# teensyMotors02_up.net
KiCad netlist of a schematic drawn in EAGLE
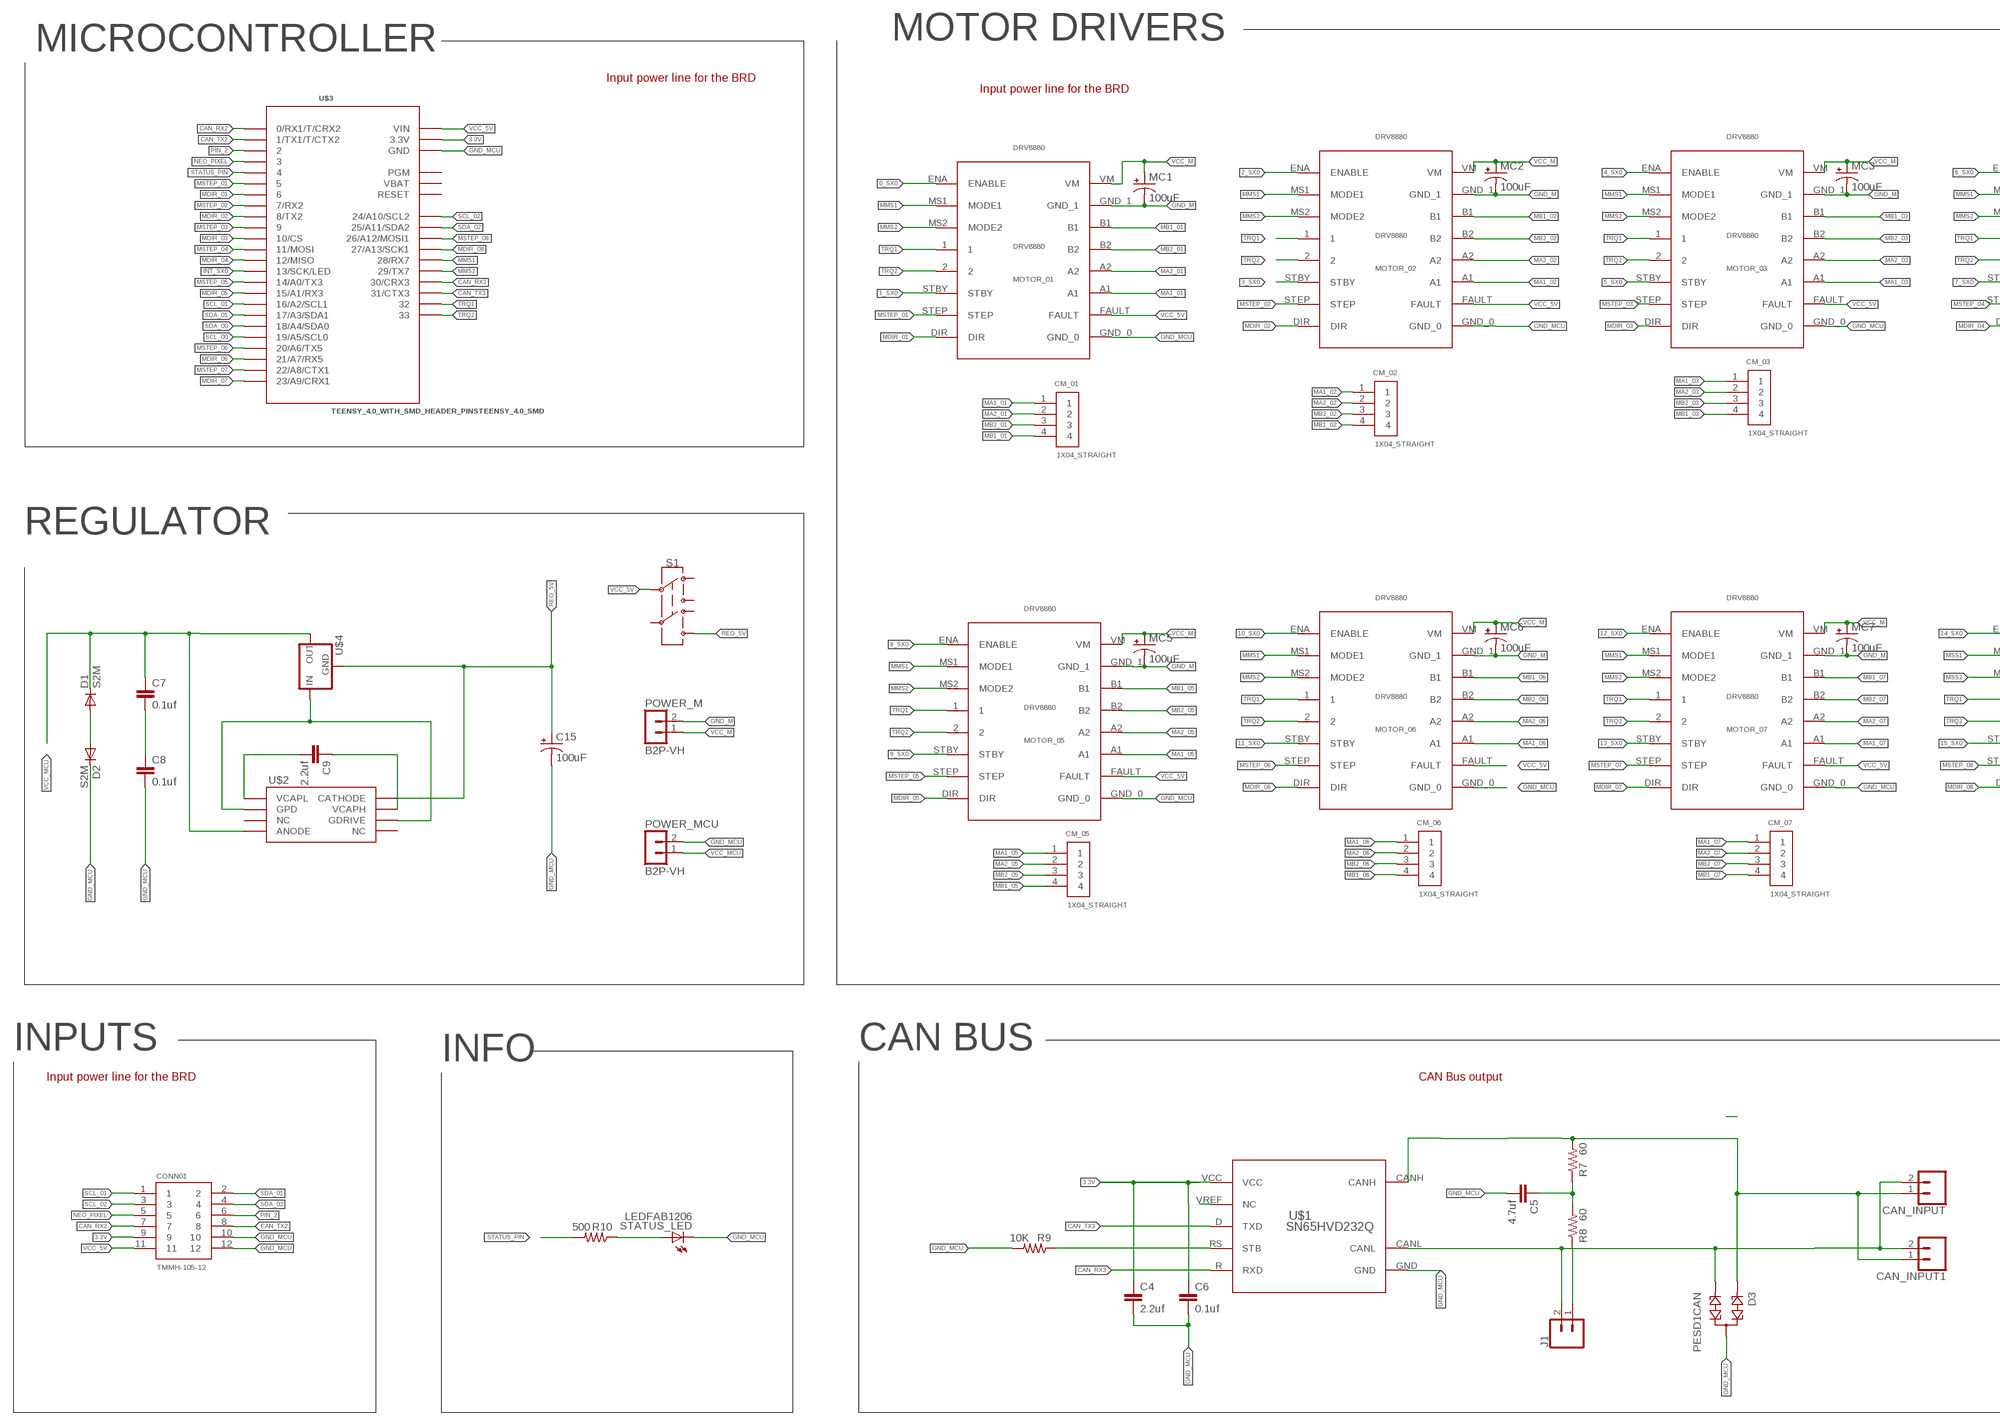
[diagram p0: schematic, sheet 1, part 1 of 2]
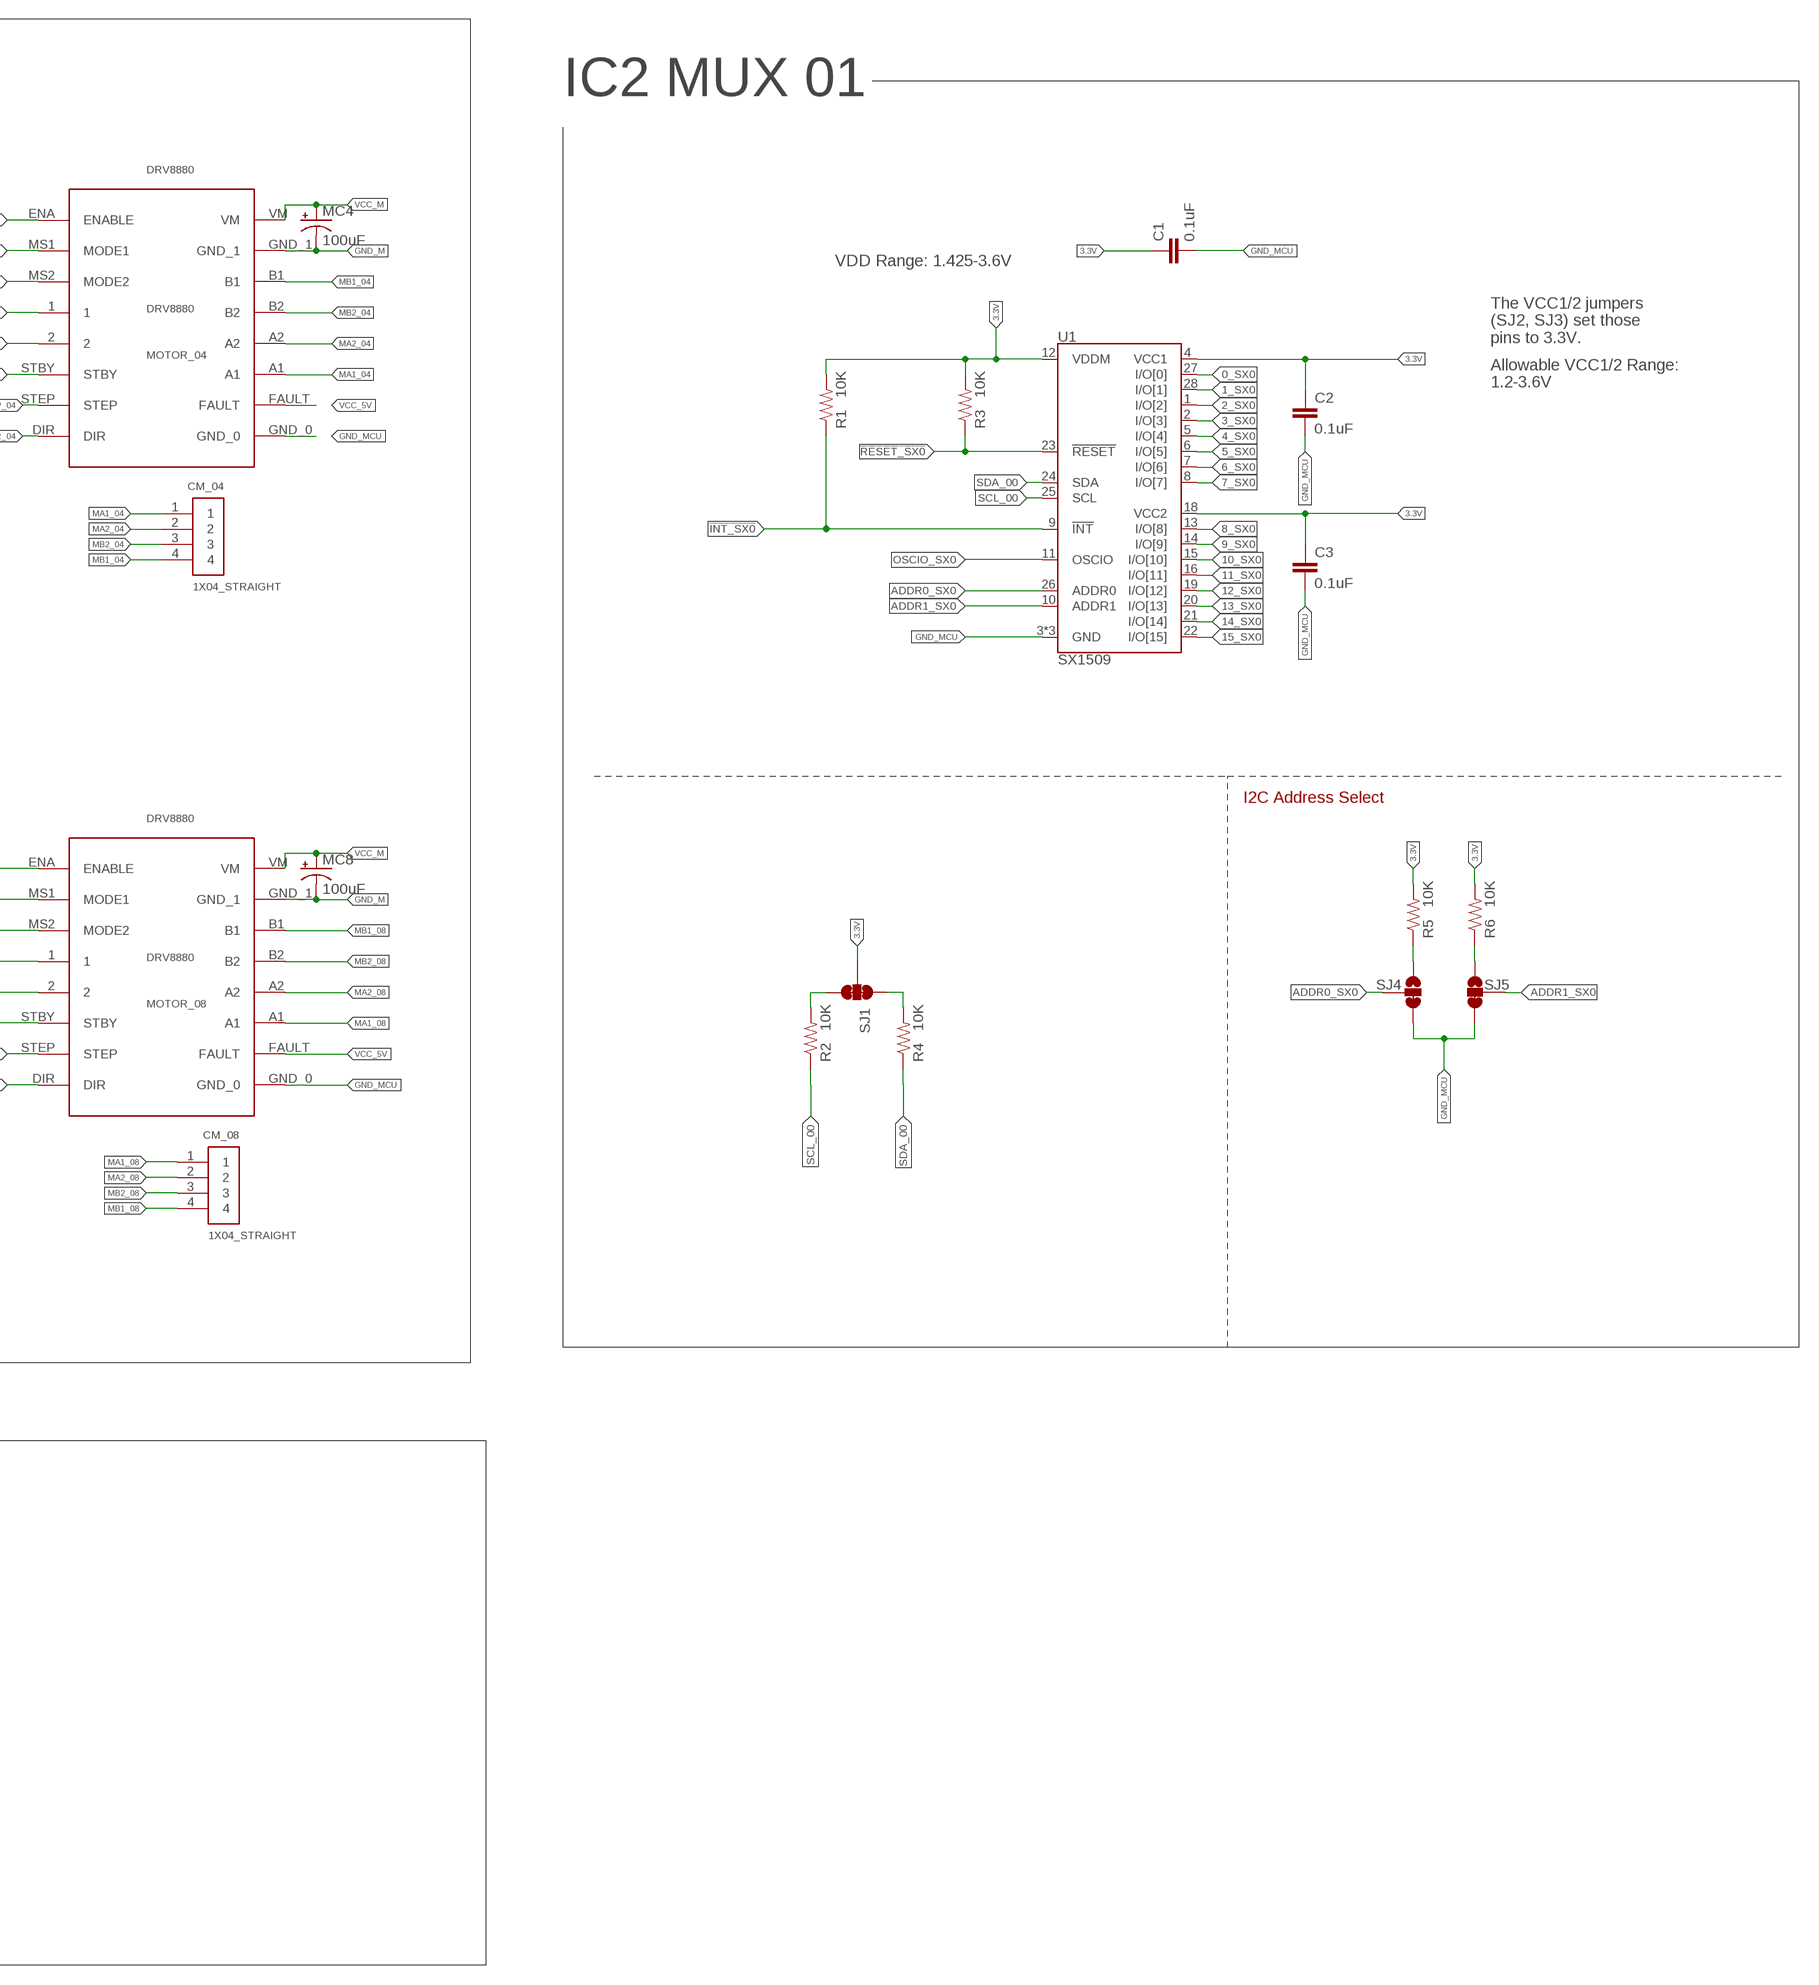
[diagram p1: schematic, sheet 1, part 2 of 2]

(export (version "E")
  (design (tool "Eeschema 10.0.6"))
  (components
    (comp (ref "C1")
      (value "0.1uF")
      (footprint "eagle-import:0603-CAP")
      (libsource (lib "eagle-import") (part "0.1UF-25V(+80/-20%)(0603)"))
    )
    (comp (ref "C2")
      (value "0.1uF")
      (footprint "eagle-import:0603-CAP")
      (libsource (lib "eagle-import") (part "0.1UF-25V(+80/-20%)(0603)"))
    )
    (comp (ref "C3")
      (value "0.1uF")
      (footprint "eagle-import:0603-CAP")
      (libsource (lib "eagle-import") (part "0.1UF-25V(+80/-20%)(0603)"))
    )
    (comp (ref "C4")
      (value "2.2uf")
      (footprint "eagle-import:0603-CAP")
      (libsource (lib "eagle-import") (part "0.1UF-25V(+80/-20%)(0603)"))
    )
    (comp (ref "C5")
      (value "4.7uf")
      (footprint "eagle-import:0603-CAP")
      (libsource (lib "eagle-import") (part "0.1UF-25V(+80/-20%)(0603)"))
    )
    (comp (ref "C6")
      (value "0.1uf")
      (footprint "eagle-import:0603-CAP")
      (libsource (lib "eagle-import") (part "0.1UF-25V(+80/-20%)(0603)"))
    )
    (comp (ref "C7")
      (value "0.1uf")
      (footprint "eagle-import:0603-CAP")
      (libsource (lib "eagle-import") (part "0.1UF-25V(+80/-20%)(0603)"))
    )
    (comp (ref "C8")
      (value "0.1uf")
      (footprint "eagle-import:0603-CAP")
      (libsource (lib "eagle-import") (part "0.1UF-25V(+80/-20%)(0603)"))
    )
    (comp (ref "C9")
      (value "2.2uf")
      (footprint "eagle-import:0603-CAP")
      (libsource (lib "eagle-import") (part "0.1UF-25V(+80/-20%)(0603)"))
    )
    (comp (ref "C15")
      (value "100uF")
      (footprint "eagle-import:PANASONIC_D")
      (libsource (lib "eagle-import") (part "100UF-POLAR-25V-20%(ELEC)"))
    )
    (comp (ref "CAN_INPUT")
      (value "CONN_02-JST-2MM-SMT")
      (footprint "eagle-import:JST-2-SMD")
      (libsource (lib "eagle-import") (part "CONN_02-JST-2MM-SMT"))
    )
    (comp (ref "CAN_INPUT1")
      (value "CONN_02-JST-2MM-SMT")
      (footprint "eagle-import:JST-2-SMD")
      (libsource (lib "eagle-import") (part "CONN_02-JST-2MM-SMT"))
    )
    (comp (ref "CM_01")
      (value "1X04_STRAIGHT")
      (footprint "eagle-import:1X04-CLEANBIG")
      (libsource (lib "eagle-import") (part "1X4-CLEANBIG"))
    )
    (comp (ref "CM_02")
      (value "1X04_STRAIGHT")
      (footprint "eagle-import:1X04-CLEANBIG")
      (libsource (lib "eagle-import") (part "1X4-CLEANBIG"))
    )
    (comp (ref "CM_03")
      (value "1X04_STRAIGHT")
      (footprint "eagle-import:1X04-CLEANBIG")
      (libsource (lib "eagle-import") (part "1X4-CLEANBIG"))
    )
    (comp (ref "CM_04")
      (value "1X04_STRAIGHT")
      (footprint "eagle-import:1X04-CLEANBIG")
      (libsource (lib "eagle-import") (part "1X4-CLEANBIG"))
    )
    (comp (ref "CM_05")
      (value "1X04_STRAIGHT")
      (footprint "eagle-import:1X04-CLEANBIG")
      (libsource (lib "eagle-import") (part "1X4-CLEANBIG"))
    )
    (comp (ref "CM_06")
      (value "1X04_STRAIGHT")
      (footprint "eagle-import:1X04-CLEANBIG")
      (libsource (lib "eagle-import") (part "1X4-CLEANBIG"))
    )
    (comp (ref "CM_07")
      (value "1X04_STRAIGHT")
      (footprint "eagle-import:1X04-CLEANBIG")
      (libsource (lib "eagle-import") (part "1X4-CLEANBIG"))
    )
    (comp (ref "CM_08")
      (value "1X04_STRAIGHT")
      (footprint "eagle-import:1X04-CLEANBIG")
      (libsource (lib "eagle-import") (part "1X4-CLEANBIG"))
    )
    (comp (ref "CONN01")
      (value "TMMH-105-12")
      (footprint "eagle-import:TMMH-105-12")
      (libsource (lib "eagle-import") (part "TMMH-105-12"))
    )
    (comp (ref "D1")
      (value "S2M")
      (footprint "eagle-import:DO214AA")
      (fields (field (name "MF") "Fairchild"))
      (libsource (lib "eagle-import") (part "S2M"))
    )
    (comp (ref "D2")
      (value "S2M")
      (footprint "eagle-import:DO214AA")
      (fields (field (name "MF") "Fairchild"))
      (libsource (lib "eagle-import") (part "S2M"))
    )
    (comp (ref "D3")
      (value "PESD1CAN")
      (footprint "eagle-import:SOT23")
      (libsource (lib "eagle-import") (part "PESD1CAN"))
    )
    (comp (ref "J1")
      (value "CONN_02")
      (footprint "eagle-import:1X02")
      (libsource (lib "eagle-import") (part "CONN_02"))
    )
    (comp (ref "MC1")
      (value "100uF")
      (footprint "eagle-import:PANASONIC_D")
      (libsource (lib "eagle-import") (part "100UF-POLAR-25V-20%(ELEC)"))
    )
    (comp (ref "MC2")
      (value "100uF")
      (footprint "eagle-import:PANASONIC_D")
      (libsource (lib "eagle-import") (part "100UF-POLAR-25V-20%(ELEC)"))
    )
    (comp (ref "MC3")
      (value "100uF")
      (footprint "eagle-import:PANASONIC_D")
      (libsource (lib "eagle-import") (part "100UF-POLAR-25V-20%(ELEC)"))
    )
    (comp (ref "MC4")
      (value "100uF")
      (footprint "eagle-import:PANASONIC_D")
      (libsource (lib "eagle-import") (part "100UF-POLAR-25V-20%(ELEC)"))
    )
    (comp (ref "MC5")
      (value "100uF")
      (footprint "eagle-import:PANASONIC_D")
      (libsource (lib "eagle-import") (part "100UF-POLAR-25V-20%(ELEC)"))
    )
    (comp (ref "MC6")
      (value "100uF")
      (footprint "eagle-import:PANASONIC_D")
      (libsource (lib "eagle-import") (part "100UF-POLAR-25V-20%(ELEC)"))
    )
    (comp (ref "MC7")
      (value "100uF")
      (footprint "eagle-import:PANASONIC_D")
      (libsource (lib "eagle-import") (part "100UF-POLAR-25V-20%(ELEC)"))
    )
    (comp (ref "MC8")
      (value "100uF")
      (footprint "eagle-import:PANASONIC_D")
      (libsource (lib "eagle-import") (part "100UF-POLAR-25V-20%(ELEC)"))
    )
    (comp (ref "MOTOR_01")
      (value "DRV8880")
      (footprint "eagle-import:DRV8880")
      (libsource (lib "eagle-import") (part "DRV8880"))
    )
    (comp (ref "MOTOR_02")
      (value "DRV8880")
      (footprint "eagle-import:DRV8880")
      (libsource (lib "eagle-import") (part "DRV8880"))
    )
    (comp (ref "MOTOR_03")
      (value "DRV8880")
      (footprint "eagle-import:DRV8880")
      (libsource (lib "eagle-import") (part "DRV8880"))
    )
    (comp (ref "MOTOR_04")
      (value "DRV8880")
      (footprint "eagle-import:DRV8880")
      (libsource (lib "eagle-import") (part "DRV8880"))
    )
    (comp (ref "MOTOR_05")
      (value "DRV8880")
      (footprint "eagle-import:DRV8880")
      (libsource (lib "eagle-import") (part "DRV8880"))
    )
    (comp (ref "MOTOR_06")
      (value "DRV8880")
      (footprint "eagle-import:DRV8880")
      (libsource (lib "eagle-import") (part "DRV8880"))
    )
    (comp (ref "MOTOR_07")
      (value "DRV8880")
      (footprint "eagle-import:DRV8880")
      (libsource (lib "eagle-import") (part "DRV8880"))
    )
    (comp (ref "MOTOR_08")
      (value "DRV8880")
      (footprint "eagle-import:DRV8880")
      (libsource (lib "eagle-import") (part "DRV8880"))
    )
    (comp (ref "POWER_M")
      (value "B2P-VH")
      (footprint "eagle-import:B2P-VH")
      (libsource (lib "eagle-import") (part "B2P-VH"))
    )
    (comp (ref "POWER_MCU")
      (value "B2P-VH")
      (footprint "eagle-import:B2P-VH")
      (libsource (lib "eagle-import") (part "B2P-VH"))
    )
    (comp (ref "R1")
      (value "10K")
      (footprint "eagle-import:0603-RES")
      (libsource (lib "eagle-import") (part "10KOHM-1/10W-1%(0603)0603"))
    )
    (comp (ref "R2")
      (value "10K")
      (footprint "eagle-import:0603-RES")
      (libsource (lib "eagle-import") (part "10KOHM-1/10W-1%(0603)0603"))
    )
    (comp (ref "R3")
      (value "10K")
      (footprint "eagle-import:0603-RES")
      (libsource (lib "eagle-import") (part "10KOHM-1/10W-1%(0603)0603"))
    )
    (comp (ref "R4")
      (value "10K")
      (footprint "eagle-import:0603-RES")
      (libsource (lib "eagle-import") (part "10KOHM-1/10W-1%(0603)0603"))
    )
    (comp (ref "R5")
      (value "10K")
      (footprint "eagle-import:0603-RES")
      (libsource (lib "eagle-import") (part "10KOHM-1/10W-1%(0603)0603"))
    )
    (comp (ref "R6")
      (value "10K")
      (footprint "eagle-import:0603-RES")
      (libsource (lib "eagle-import") (part "10KOHM-1/10W-1%(0603)0603"))
    )
    (comp (ref "R7")
      (value "60")
      (footprint "eagle-import:0603-RES")
      (libsource (lib "eagle-import") (part "10KOHM-1/10W-1%(0603)0603"))
    )
    (comp (ref "R8")
      (value "60")
      (footprint "eagle-import:0603-RES")
      (libsource (lib "eagle-import") (part "10KOHM-1/10W-1%(0603)0603"))
    )
    (comp (ref "R9")
      (value "10K")
      (footprint "eagle-import:0603-RES")
      (libsource (lib "eagle-import") (part "10KOHM-1/10W-1%(0603)0603"))
    )
    (comp (ref "R10")
      (value "500")
      (footprint "eagle-import:0603-RES")
      (libsource (lib "eagle-import") (part "10KOHM-1/10W-1%(0603)0603"))
    )
    (comp (ref "S1")
      (value "SWITCH-DPDT-SMD-AYZ0202")
      (footprint "eagle-import:SWITCH_DPDT_SMD_AYZ0202")
      (fields (field (name "SPICEPREFIX") "X"))
      (libsource (lib "eagle-import") (part "SWITCH-DPDT-SMD-AYZ0202"))
    )
    (comp (ref "SJ1")
      (value "JUMPER-PAD-3-NC_BY_TRACE")
      (footprint "eagle-import:PAD-JUMPER-3-3OF3_NC_BY_TRACE_YES_SILK_FULL_BOX")
      (libsource (lib "eagle-import") (part "JUMPER-PAD-3-NC_BY_TRACE"))
    )
    (comp (ref "SJ4")
      (value "JUMPER-PAD-3-2OF3_NC_BY_TRACE_SMALL")
      (footprint "eagle-import:PAD-JUMPER-3-2OF3_NC_BY_TRACE_YES_SILK_FULL_BOX")
      (libsource (lib "eagle-import") (part "JUMPER-PAD-3-2OF3_NC_BY_TRACE_SMALL"))
    )
    (comp (ref "SJ5")
      (value "JUMPER-PAD-3-2OF3_NC_BY_TRACE_SMALL")
      (footprint "eagle-import:PAD-JUMPER-3-2OF3_NC_BY_TRACE_YES_SILK_FULL_BOX")
      (libsource (lib "eagle-import") (part "JUMPER-PAD-3-2OF3_NC_BY_TRACE_SMALL"))
    )
    (comp (ref "STATUS_LED")
      (value "LEDFAB1206")
      (footprint "eagle-import:LED1206FAB")
      (libsource (lib "eagle-import") (part "LEDFAB1206"))
    )
    (comp (ref "U$1")
      (value "SN65HVD232Q")
      (footprint "eagle-import:SN65HVD232Q")
      (libsource (lib "eagle-import") (part "SN65HVD232Q"))
    )
    (comp (ref "U$2")
      (value "LM74610-Q1")
      (footprint "eagle-import:VSSOP(8)")
      (fields (field (name "MPN") "LM74610-Q1 "))
      (libsource (lib "eagle-import") (part "LM74610-Q1"))
    )
    (comp (ref "U$3")
      (value "TEENSY_4.0_WITH_SMD_HEADER_PINSTEENSY_4.0_SMD")
      (footprint "eagle-import:TEENSY_4.0_SMD")
      (libsource (lib "eagle-import") (part "TEENSY_4.0_WITH_SMD_HEADER_PINSTEENSY_4.0_SMD"))
    )
    (comp (ref "U$4")
      (value "BUK")
      (footprint "eagle-import:TO263-3")
      (libsource (lib "eagle-import") (part "BUK"))
    )
    (comp (ref "U1")
      (value "SX1509")
      (footprint "eagle-import:QFN-28")
      (libsource (lib "eagle-import") (part "SX1509"))
    )
  )
  (nets
    (net (code "1") (name "0_SX0") (class "Default")
      (node (ref "MOTOR_01") (pin "ENA") (pinfunction "ENABLE_ENA") (pintype "bidirectional"))
      (node (ref "U1") (pin "27") (pinfunction "I/O[0]_27") (pintype "bidirectional"))
    )
    (net (code "2") (name "1_SX0") (class "Default")
      (node (ref "MOTOR_01") (pin "STBY") (pinfunction "STBY_STBY") (pintype "bidirectional"))
      (node (ref "U1") (pin "28") (pinfunction "I/O[1]_28") (pintype "bidirectional"))
    )
    (net (code "3") (name "2_SX0") (class "Default")
      (node (ref "MOTOR_02") (pin "ENA") (pinfunction "ENABLE_ENA") (pintype "bidirectional"))
      (node (ref "U1") (pin "1") (pinfunction "I/O[2]_1") (pintype "bidirectional"))
    )
    (net (code "4") (name "3.3V") (class "Default")
      (node (ref "C1") (pin "1") (pinfunction "1_1") (pintype "passive"))
      (node (ref "C2") (pin "1") (pinfunction "1_1") (pintype "passive"))
      (node (ref "C3") (pin "1") (pinfunction "1_1") (pintype "passive"))
      (node (ref "C4") (pin "1") (pinfunction "1_1") (pintype "passive"))
      (node (ref "C6") (pin "1") (pinfunction "1_1") (pintype "passive"))
      (node (ref "CONN01") (pin "9") (pinfunction "9_9") (pintype "bidirectional"))
      (node (ref "R1") (pin "2") (pinfunction "2_2") (pintype "passive"))
      (node (ref "R3") (pin "2") (pinfunction "2_2") (pintype "passive"))
      (node (ref "R5") (pin "2") (pinfunction "2_2") (pintype "passive"))
      (node (ref "R6") (pin "2") (pinfunction "2_2") (pintype "passive"))
      (node (ref "SJ1") (pin "2") (pinfunction "2_2") (pintype "passive"))
      (node (ref "U$1") (pin "VCC") (pinfunction "VCC_VCC") (pintype "power_in"))
      (node (ref "U$3") (pin "3.3V") (pinfunction "3.3V_3.3V") (pintype "power_in"))
      (node (ref "U$3") (pin "3.3V1") (pinfunction "3.3V_3.3V1") (pintype "power_in"))
      (node (ref "U1") (pin "12") (pinfunction "VDDM_12") (pintype "bidirectional"))
      (node (ref "U1") (pin "18") (pinfunction "VCC2_18") (pintype "bidirectional"))
      (node (ref "U1") (pin "4") (pinfunction "VCC1_4") (pintype "bidirectional"))
    )
    (net (code "5") (name "3_SX0") (class "Default")
      (node (ref "MOTOR_02") (pin "STBY") (pinfunction "STBY_STBY") (pintype "bidirectional"))
      (node (ref "U1") (pin "2") (pinfunction "I/O[3]_2") (pintype "bidirectional"))
    )
    (net (code "6") (name "4_SX0") (class "Default")
      (node (ref "MOTOR_03") (pin "ENA") (pinfunction "ENABLE_ENA") (pintype "bidirectional"))
      (node (ref "U1") (pin "5") (pinfunction "I/O[4]_5") (pintype "bidirectional"))
    )
    (net (code "7") (name "5_SX0") (class "Default")
      (node (ref "MOTOR_03") (pin "STBY") (pinfunction "STBY_STBY") (pintype "bidirectional"))
      (node (ref "U1") (pin "6") (pinfunction "I/O[5]_6") (pintype "bidirectional"))
    )
    (net (code "8") (name "6_SX0") (class "Default")
      (node (ref "MOTOR_04") (pin "ENA") (pinfunction "ENABLE_ENA") (pintype "bidirectional"))
      (node (ref "U1") (pin "7") (pinfunction "I/O[6]_7") (pintype "bidirectional"))
    )
    (net (code "9") (name "7_SX0") (class "Default")
      (node (ref "MOTOR_04") (pin "STBY") (pinfunction "STBY_STBY") (pintype "bidirectional"))
      (node (ref "U1") (pin "8") (pinfunction "I/O[7]_8") (pintype "bidirectional"))
    )
    (net (code "10") (name "8_SX0") (class "Default")
      (node (ref "MOTOR_05") (pin "ENA") (pinfunction "ENABLE_ENA") (pintype "bidirectional"))
      (node (ref "U1") (pin "13") (pinfunction "I/O[8]_13") (pintype "bidirectional"))
    )
    (net (code "11") (name "9_SX0") (class "Default")
      (node (ref "MOTOR_05") (pin "STBY") (pinfunction "STBY_STBY") (pintype "bidirectional"))
      (node (ref "U1") (pin "14") (pinfunction "I/O[9]_14") (pintype "bidirectional"))
    )
    (net (code "12") (name "10_SX0") (class "Default")
      (node (ref "MOTOR_06") (pin "ENA") (pinfunction "ENABLE_ENA") (pintype "bidirectional"))
      (node (ref "U1") (pin "15") (pinfunction "I/O[10]_15") (pintype "bidirectional"))
    )
    (net (code "13") (name "11_SX0") (class "Default")
      (node (ref "MOTOR_06") (pin "STBY") (pinfunction "STBY_STBY") (pintype "bidirectional"))
      (node (ref "U1") (pin "16") (pinfunction "I/O[11]_16") (pintype "bidirectional"))
    )
    (net (code "14") (name "12_SX0") (class "Default")
      (node (ref "MOTOR_07") (pin "ENA") (pinfunction "ENABLE_ENA") (pintype "bidirectional"))
      (node (ref "U1") (pin "19") (pinfunction "I/O[12]_19") (pintype "bidirectional"))
    )
    (net (code "15") (name "13_SX0") (class "Default")
      (node (ref "MOTOR_07") (pin "STBY") (pinfunction "STBY_STBY") (pintype "bidirectional"))
      (node (ref "U1") (pin "20") (pinfunction "I/O[13]_20") (pintype "bidirectional"))
    )
    (net (code "16") (name "14_SX0") (class "Default")
      (node (ref "MOTOR_08") (pin "ENA") (pinfunction "ENABLE_ENA") (pintype "bidirectional"))
      (node (ref "U1") (pin "21") (pinfunction "I/O[14]_21") (pintype "bidirectional"))
    )
    (net (code "17") (name "15_SX0") (class "Default")
      (node (ref "MOTOR_08") (pin "STBY") (pinfunction "STBY_STBY") (pintype "bidirectional"))
      (node (ref "U1") (pin "22") (pinfunction "I/O[15]_22") (pintype "bidirectional"))
    )
    (net (code "18") (name "ADDR0_SX0") (class "Default")
      (node (ref "SJ4") (pin "2") (pinfunction "2_2") (pintype "passive"))
      (node (ref "U1") (pin "26") (pinfunction "ADDR0_26") (pintype "bidirectional"))
    )
    (net (code "19") (name "ADDR1_SX0") (class "Default")
      (node (ref "SJ5") (pin "2") (pinfunction "2_2") (pintype "passive"))
      (node (ref "U1") (pin "10") (pinfunction "ADDR1_10") (pintype "bidirectional"))
    )
    (net (code "20") (name "CAN_RX2") (class "Default")
      (node (ref "CONN01") (pin "7") (pinfunction "7_7") (pintype "bidirectional"))
      (node (ref "U$3") (pin "0") (pinfunction "0/RX1/T/CRX2_0") (pintype "bidirectional"))
    )
    (net (code "21") (name "CAN_RX3") (class "Default")
      (node (ref "U$1") (pin "R") (pinfunction "RXD_R") (pintype "output"))
      (node (ref "U$3") (pin "30") (pinfunction "30/CRX3_30") (pintype "bidirectional"))
    )
    (net (code "22") (name "CAN_TX2") (class "Default")
      (node (ref "CONN01") (pin "8") (pinfunction "8_8") (pintype "bidirectional"))
      (node (ref "U$3") (pin "1") (pinfunction "1/TX1/T/CTX2_1") (pintype "bidirectional"))
    )
    (net (code "23") (name "CAN_TX3") (class "Default")
      (node (ref "U$1") (pin "D") (pinfunction "TXD_D") (pintype "input"))
      (node (ref "U$3") (pin "31") (pinfunction "31/CTX3_31") (pintype "bidirectional"))
    )
    (net (code "24") (name "GND_M") (class "Default")
      (node (ref "MC1") (pin "-") (pinfunction "-_-") (pintype "passive"))
      (node (ref "MC2") (pin "-") (pinfunction "-_-") (pintype "passive"))
      (node (ref "MC3") (pin "-") (pinfunction "-_-") (pintype "passive"))
      (node (ref "MC4") (pin "-") (pinfunction "-_-") (pintype "passive"))
      (node (ref "MC5") (pin "-") (pinfunction "-_-") (pintype "passive"))
      (node (ref "MC6") (pin "-") (pinfunction "-_-") (pintype "passive"))
      (node (ref "MC7") (pin "-") (pinfunction "-_-") (pintype "passive"))
      (node (ref "MC8") (pin "-") (pinfunction "-_-") (pintype "passive"))
      (node (ref "MOTOR_01") (pin "GND_1") (pinfunction "GND_1_GND_1") (pintype "bidirectional"))
      (node (ref "MOTOR_02") (pin "GND_1") (pinfunction "GND_1_GND_1") (pintype "bidirectional"))
      (node (ref "MOTOR_03") (pin "GND_1") (pinfunction "GND_1_GND_1") (pintype "bidirectional"))
      (node (ref "MOTOR_04") (pin "GND_1") (pinfunction "GND_1_GND_1") (pintype "bidirectional"))
      (node (ref "MOTOR_05") (pin "GND_1") (pinfunction "GND_1_GND_1") (pintype "bidirectional"))
      (node (ref "MOTOR_06") (pin "GND_1") (pinfunction "GND_1_GND_1") (pintype "bidirectional"))
      (node (ref "MOTOR_07") (pin "GND_1") (pinfunction "GND_1_GND_1") (pintype "bidirectional"))
      (node (ref "MOTOR_08") (pin "GND_1") (pinfunction "GND_1_GND_1") (pintype "bidirectional"))
      (node (ref "POWER_M") (pin "2") (pinfunction "2_2") (pintype "passive"))
    )
    (net (code "25") (name "GND_MCU") (class "Default")
      (node (ref "C1") (pin "2") (pinfunction "2_2") (pintype "passive"))
      (node (ref "C15") (pin "-") (pinfunction "-_-") (pintype "passive"))
      (node (ref "C2") (pin "2") (pinfunction "2_2") (pintype "passive"))
      (node (ref "C3") (pin "2") (pinfunction "2_2") (pintype "passive"))
      (node (ref "C4") (pin "2") (pinfunction "2_2") (pintype "passive"))
      (node (ref "C5") (pin "2") (pinfunction "2_2") (pintype "passive"))
      (node (ref "C6") (pin "2") (pinfunction "2_2") (pintype "passive"))
      (node (ref "C8") (pin "2") (pinfunction "2_2") (pintype "passive"))
      (node (ref "CONN01") (pin "10") (pinfunction "10_10") (pintype "bidirectional"))
      (node (ref "CONN01") (pin "12") (pinfunction "12_12") (pintype "bidirectional"))
      (node (ref "D2") (pin "C") (pinfunction "C_C") (pintype "passive"))
      (node (ref "D3") (pin "3") (pinfunction "3_3") (pintype "passive"))
      (node (ref "MOTOR_01") (pin "GND_0") (pinfunction "GND_0_GND_0") (pintype "bidirectional"))
      (node (ref "MOTOR_02") (pin "GND_0") (pinfunction "GND_0_GND_0") (pintype "bidirectional"))
      (node (ref "MOTOR_03") (pin "GND_0") (pinfunction "GND_0_GND_0") (pintype "bidirectional"))
      (node (ref "MOTOR_04") (pin "GND_0") (pinfunction "GND_0_GND_0") (pintype "bidirectional"))
      (node (ref "MOTOR_05") (pin "GND_0") (pinfunction "GND_0_GND_0") (pintype "bidirectional"))
      (node (ref "MOTOR_06") (pin "GND_0") (pinfunction "GND_0_GND_0") (pintype "bidirectional"))
      (node (ref "MOTOR_07") (pin "GND_0") (pinfunction "GND_0_GND_0") (pintype "bidirectional"))
      (node (ref "MOTOR_08") (pin "GND_0") (pinfunction "GND_0_GND_0") (pintype "bidirectional"))
      (node (ref "POWER_MCU") (pin "2") (pinfunction "2_2") (pintype "passive"))
      (node (ref "R9") (pin "2") (pinfunction "2_2") (pintype "passive"))
      (node (ref "SJ4") (pin "3") (pinfunction "3_3") (pintype "passive"))
      (node (ref "SJ5") (pin "3") (pinfunction "3_3") (pintype "passive"))
      (node (ref "STATUS_LED") (pin "2") (pinfunction "C_2") (pintype "passive"))
      (node (ref "U$1") (pin "GND") (pinfunction "GND_GND") (pintype "power_in"))
      (node (ref "U$3") (pin "GND") (pinfunction "GND_GND") (pintype "power_in"))
      (node (ref "U$3") (pin "GND1") (pinfunction "GND_GND1") (pintype "power_in"))
      (node (ref "U$3") (pin "GND2") (pinfunction "GND_GND2") (pintype "power_in"))
      (node (ref "U1") (pin "17") (pinfunction "GND_17") (pintype "bidirectional"))
      (node (ref "U1") (pin "29") (pinfunction "GND_29") (pintype "bidirectional"))
      (node (ref "U1") (pin "3") (pinfunction "GND_3") (pintype "bidirectional"))
    )
    (net (code "26") (name "MA1_01") (class "Default")
      (node (ref "CM_01") (pin "1") (pinfunction "1_1") (pintype "bidirectional"))
      (node (ref "MOTOR_01") (pin "A1") (pinfunction "A1_A1") (pintype "bidirectional"))
    )
    (net (code "27") (name "MA1_02") (class "Default")
      (node (ref "CM_02") (pin "1") (pinfunction "1_1") (pintype "bidirectional"))
      (node (ref "MOTOR_02") (pin "A1") (pinfunction "A1_A1") (pintype "bidirectional"))
    )
    (net (code "28") (name "MA1_03") (class "Default")
      (node (ref "CM_03") (pin "1") (pinfunction "1_1") (pintype "bidirectional"))
      (node (ref "MOTOR_03") (pin "A1") (pinfunction "A1_A1") (pintype "bidirectional"))
    )
    (net (code "29") (name "MA1_04") (class "Default")
      (node (ref "CM_04") (pin "1") (pinfunction "1_1") (pintype "bidirectional"))
      (node (ref "MOTOR_04") (pin "A1") (pinfunction "A1_A1") (pintype "bidirectional"))
    )
    (net (code "30") (name "MA1_05") (class "Default")
      (node (ref "CM_05") (pin "1") (pinfunction "1_1") (pintype "bidirectional"))
      (node (ref "MOTOR_05") (pin "A1") (pinfunction "A1_A1") (pintype "bidirectional"))
    )
    (net (code "31") (name "MA1_06") (class "Default")
      (node (ref "CM_06") (pin "1") (pinfunction "1_1") (pintype "bidirectional"))
      (node (ref "MOTOR_06") (pin "A1") (pinfunction "A1_A1") (pintype "bidirectional"))
    )
    (net (code "32") (name "MA1_07") (class "Default")
      (node (ref "CM_07") (pin "1") (pinfunction "1_1") (pintype "bidirectional"))
      (node (ref "MOTOR_07") (pin "A1") (pinfunction "A1_A1") (pintype "bidirectional"))
    )
    (net (code "33") (name "MA1_08") (class "Default")
      (node (ref "CM_08") (pin "1") (pinfunction "1_1") (pintype "bidirectional"))
      (node (ref "MOTOR_08") (pin "A1") (pinfunction "A1_A1") (pintype "bidirectional"))
    )
    (net (code "34") (name "MA2_01") (class "Default")
      (node (ref "CM_01") (pin "2") (pinfunction "2_2") (pintype "bidirectional"))
      (node (ref "MOTOR_01") (pin "A2") (pinfunction "A2_A2") (pintype "bidirectional"))
    )
    (net (code "35") (name "MA2_02") (class "Default")
      (node (ref "CM_02") (pin "2") (pinfunction "2_2") (pintype "bidirectional"))
      (node (ref "MOTOR_02") (pin "A2") (pinfunction "A2_A2") (pintype "bidirectional"))
    )
    (net (code "36") (name "MA2_03") (class "Default")
      (node (ref "CM_03") (pin "2") (pinfunction "2_2") (pintype "bidirectional"))
      (node (ref "MOTOR_03") (pin "A2") (pinfunction "A2_A2") (pintype "bidirectional"))
    )
    (net (code "37") (name "MA2_04") (class "Default")
      (node (ref "CM_04") (pin "2") (pinfunction "2_2") (pintype "bidirectional"))
      (node (ref "MOTOR_04") (pin "A2") (pinfunction "A2_A2") (pintype "bidirectional"))
    )
    (net (code "38") (name "MA2_05") (class "Default")
      (node (ref "CM_05") (pin "2") (pinfunction "2_2") (pintype "bidirectional"))
      (node (ref "MOTOR_05") (pin "A2") (pinfunction "A2_A2") (pintype "bidirectional"))
    )
    (net (code "39") (name "MA2_06") (class "Default")
      (node (ref "CM_06") (pin "2") (pinfunction "2_2") (pintype "bidirectional"))
      (node (ref "MOTOR_06") (pin "A2") (pinfunction "A2_A2") (pintype "bidirectional"))
    )
    (net (code "40") (name "MA2_07") (class "Default")
      (node (ref "CM_07") (pin "2") (pinfunction "2_2") (pintype "bidirectional"))
      (node (ref "MOTOR_07") (pin "A2") (pinfunction "A2_A2") (pintype "bidirectional"))
    )
    (net (code "41") (name "MA2_08") (class "Default")
      (node (ref "CM_08") (pin "2") (pinfunction "2_2") (pintype "bidirectional"))
      (node (ref "MOTOR_08") (pin "A2") (pinfunction "A2_A2") (pintype "bidirectional"))
    )
    (net (code "42") (name "MB1_01") (class "Default")
      (node (ref "CM_01") (pin "4") (pinfunction "4_4") (pintype "bidirectional"))
      (node (ref "MOTOR_01") (pin "B1") (pinfunction "B1_B1") (pintype "bidirectional"))
    )
    (net (code "43") (name "MB1_02") (class "Default")
      (node (ref "CM_02") (pin "4") (pinfunction "4_4") (pintype "bidirectional"))
      (node (ref "MOTOR_02") (pin "B1") (pinfunction "B1_B1") (pintype "bidirectional"))
    )
    (net (code "44") (name "MB1_03") (class "Default")
      (node (ref "CM_03") (pin "4") (pinfunction "4_4") (pintype "bidirectional"))
      (node (ref "MOTOR_03") (pin "B1") (pinfunction "B1_B1") (pintype "bidirectional"))
    )
    (net (code "45") (name "MB1_04") (class "Default")
      (node (ref "CM_04") (pin "4") (pinfunction "4_4") (pintype "bidirectional"))
      (node (ref "MOTOR_04") (pin "B1") (pinfunction "B1_B1") (pintype "bidirectional"))
    )
    (net (code "46") (name "MB1_05") (class "Default")
      (node (ref "CM_05") (pin "4") (pinfunction "4_4") (pintype "bidirectional"))
      (node (ref "MOTOR_05") (pin "B1") (pinfunction "B1_B1") (pintype "bidirectional"))
    )
    (net (code "47") (name "MB1_06") (class "Default")
      (node (ref "CM_06") (pin "4") (pinfunction "4_4") (pintype "bidirectional"))
      (node (ref "MOTOR_06") (pin "B1") (pinfunction "B1_B1") (pintype "bidirectional"))
    )
    (net (code "48") (name "MB1_07") (class "Default")
      (node (ref "CM_07") (pin "4") (pinfunction "4_4") (pintype "bidirectional"))
      (node (ref "MOTOR_07") (pin "B1") (pinfunction "B1_B1") (pintype "bidirectional"))
    )
    (net (code "49") (name "MB1_08") (class "Default")
      (node (ref "CM_08") (pin "4") (pinfunction "4_4") (pintype "bidirectional"))
      (node (ref "MOTOR_08") (pin "B1") (pinfunction "B1_B1") (pintype "bidirectional"))
    )
    (net (code "50") (name "MB2_01") (class "Default")
      (node (ref "CM_01") (pin "3") (pinfunction "3_3") (pintype "bidirectional"))
      (node (ref "MOTOR_01") (pin "B2") (pinfunction "B2_B2") (pintype "bidirectional"))
    )
    (net (code "51") (name "MB2_02") (class "Default")
      (node (ref "CM_02") (pin "3") (pinfunction "3_3") (pintype "bidirectional"))
      (node (ref "MOTOR_02") (pin "B2") (pinfunction "B2_B2") (pintype "bidirectional"))
    )
    (net (code "52") (name "MB2_03") (class "Default")
      (node (ref "CM_03") (pin "3") (pinfunction "3_3") (pintype "bidirectional"))
      (node (ref "MOTOR_03") (pin "B2") (pinfunction "B2_B2") (pintype "bidirectional"))
    )
    (net (code "53") (name "MB2_04") (class "Default")
      (node (ref "CM_04") (pin "3") (pinfunction "3_3") (pintype "bidirectional"))
      (node (ref "MOTOR_04") (pin "B2") (pinfunction "B2_B2") (pintype "bidirectional"))
    )
    (net (code "54") (name "MB2_05") (class "Default")
      (node (ref "CM_05") (pin "3") (pinfunction "3_3") (pintype "bidirectional"))
      (node (ref "MOTOR_05") (pin "B2") (pinfunction "B2_B2") (pintype "bidirectional"))
    )
    (net (code "55") (name "MB2_06") (class "Default")
      (node (ref "CM_06") (pin "3") (pinfunction "3_3") (pintype "bidirectional"))
      (node (ref "MOTOR_06") (pin "B2") (pinfunction "B2_B2") (pintype "bidirectional"))
    )
    (net (code "56") (name "MB2_07") (class "Default")
      (node (ref "CM_07") (pin "3") (pinfunction "3_3") (pintype "bidirectional"))
      (node (ref "MOTOR_07") (pin "B2") (pinfunction "B2_B2") (pintype "bidirectional"))
    )
    (net (code "57") (name "MB2_08") (class "Default")
      (node (ref "CM_08") (pin "3") (pinfunction "3_3") (pintype "bidirectional"))
      (node (ref "MOTOR_08") (pin "B2") (pinfunction "B2_B2") (pintype "bidirectional"))
    )
    (net (code "58") (name "MDIR_01") (class "Default")
      (node (ref "MOTOR_01") (pin "DIR") (pinfunction "DIR_DIR") (pintype "bidirectional"))
      (node (ref "U$3") (pin "6") (pinfunction "6_6") (pintype "bidirectional"))
    )
    (net (code "59") (name "MDIR_02") (class "Default")
      (node (ref "MOTOR_02") (pin "DIR") (pinfunction "DIR_DIR") (pintype "bidirectional"))
      (node (ref "U$3") (pin "8") (pinfunction "8/TX2_8") (pintype "bidirectional"))
    )
    (net (code "60") (name "MDIR_03") (class "Default")
      (node (ref "MOTOR_03") (pin "DIR") (pinfunction "DIR_DIR") (pintype "bidirectional"))
      (node (ref "U$3") (pin "10") (pinfunction "10/CS_10") (pintype "bidirectional"))
    )
    (net (code "61") (name "MDIR_04") (class "Default")
      (node (ref "MOTOR_04") (pin "DIR") (pinfunction "DIR_DIR") (pintype "bidirectional"))
      (node (ref "U$3") (pin "12") (pinfunction "12/MISO_12") (pintype "bidirectional"))
    )
    (net (code "62") (name "MDIR_05") (class "Default")
      (node (ref "MOTOR_05") (pin "DIR") (pinfunction "DIR_DIR") (pintype "bidirectional"))
      (node (ref "U$3") (pin "15/A1") (pinfunction "15/A1/RX3_15/A1") (pintype "bidirectional"))
    )
    (net (code "63") (name "MDIR_06") (class "Default")
      (node (ref "MOTOR_06") (pin "DIR") (pinfunction "DIR_DIR") (pintype "bidirectional"))
      (node (ref "U$3") (pin "21/A7") (pinfunction "21/A7/RX5_21/A7") (pintype "bidirectional"))
    )
    (net (code "64") (name "MDIR_07") (class "Default")
      (node (ref "MOTOR_07") (pin "DIR") (pinfunction "DIR_DIR") (pintype "bidirectional"))
      (node (ref "U$3") (pin "23/A9") (pinfunction "23/A9/CRX1_23/A9") (pintype "bidirectional"))
    )
    (net (code "65") (name "MDIR_08") (class "Default")
      (node (ref "MOTOR_08") (pin "DIR") (pinfunction "DIR_DIR") (pintype "bidirectional"))
      (node (ref "U$3") (pin "27") (pinfunction "27/A13/SCK1_27") (pintype "bidirectional"))
    )
    (net (code "66") (name "MMS1") (class "Default")
      (node (ref "MOTOR_01") (pin "MS1") (pinfunction "MODE1_MS1") (pintype "bidirectional"))
      (node (ref "MOTOR_02") (pin "MS1") (pinfunction "MODE1_MS1") (pintype "bidirectional"))
      (node (ref "MOTOR_03") (pin "MS1") (pinfunction "MODE1_MS1") (pintype "bidirectional"))
      (node (ref "MOTOR_04") (pin "MS1") (pinfunction "MODE1_MS1") (pintype "bidirectional"))
      (node (ref "MOTOR_05") (pin "MS1") (pinfunction "MODE1_MS1") (pintype "bidirectional"))
      (node (ref "MOTOR_06") (pin "MS1") (pinfunction "MODE1_MS1") (pintype "bidirectional"))
      (node (ref "MOTOR_07") (pin "MS1") (pinfunction "MODE1_MS1") (pintype "bidirectional"))
      (node (ref "U$3") (pin "28") (pinfunction "28/RX7_28") (pintype "bidirectional"))
    )
    (net (code "67") (name "MMS2") (class "Default")
      (node (ref "MOTOR_01") (pin "MS2") (pinfunction "MODE2_MS2") (pintype "bidirectional"))
      (node (ref "MOTOR_02") (pin "MS2") (pinfunction "MODE2_MS2") (pintype "bidirectional"))
      (node (ref "MOTOR_03") (pin "MS2") (pinfunction "MODE2_MS2") (pintype "bidirectional"))
      (node (ref "MOTOR_04") (pin "MS2") (pinfunction "MODE2_MS2") (pintype "bidirectional"))
      (node (ref "MOTOR_05") (pin "MS2") (pinfunction "MODE2_MS2") (pintype "bidirectional"))
      (node (ref "MOTOR_06") (pin "MS2") (pinfunction "MODE2_MS2") (pintype "bidirectional"))
      (node (ref "MOTOR_07") (pin "MS2") (pinfunction "MODE2_MS2") (pintype "bidirectional"))
      (node (ref "U$3") (pin "29") (pinfunction "29/TX7_29") (pintype "bidirectional"))
    )
    (net (code "68") (name "MSS1") (class "Default")
      (node (ref "MOTOR_08") (pin "MS1") (pinfunction "MODE1_MS1") (pintype "bidirectional"))
    )
    (net (code "69") (name "MSS2") (class "Default")
      (node (ref "MOTOR_08") (pin "MS2") (pinfunction "MODE2_MS2") (pintype "bidirectional"))
    )
    (net (code "70") (name "MSTEP_01") (class "Default")
      (node (ref "MOTOR_01") (pin "STEP") (pinfunction "STEP_STEP") (pintype "bidirectional"))
      (node (ref "U$3") (pin "5") (pinfunction "5_5") (pintype "bidirectional"))
    )
    (net (code "71") (name "MSTEP_02") (class "Default")
      (node (ref "MOTOR_02") (pin "STEP") (pinfunction "STEP_STEP") (pintype "bidirectional"))
      (node (ref "U$3") (pin "7") (pinfunction "7/RX2_7") (pintype "bidirectional"))
    )
    (net (code "72") (name "MSTEP_03") (class "Default")
      (node (ref "MOTOR_03") (pin "STEP") (pinfunction "STEP_STEP") (pintype "bidirectional"))
      (node (ref "U$3") (pin "9") (pinfunction "9_9") (pintype "bidirectional"))
    )
    (net (code "73") (name "MSTEP_04") (class "Default")
      (node (ref "MOTOR_04") (pin "STEP") (pinfunction "STEP_STEP") (pintype "bidirectional"))
      (node (ref "U$3") (pin "11") (pinfunction "11/MOSI_11") (pintype "bidirectional"))
    )
    (net (code "74") (name "MSTEP_05") (class "Default")
      (node (ref "MOTOR_05") (pin "STEP") (pinfunction "STEP_STEP") (pintype "bidirectional"))
      (node (ref "U$3") (pin "14/A0") (pinfunction "14/A0/TX3_14/A0") (pintype "bidirectional"))
    )
    (net (code "75") (name "MSTEP_06") (class "Default")
      (node (ref "MOTOR_06") (pin "STEP") (pinfunction "STEP_STEP") (pintype "bidirectional"))
      (node (ref "U$3") (pin "20/A6") (pinfunction "20/A6/TX5_20/A6") (pintype "bidirectional"))
    )
    (net (code "76") (name "MSTEP_07") (class "Default")
      (node (ref "MOTOR_07") (pin "STEP") (pinfunction "STEP_STEP") (pintype "bidirectional"))
      (node (ref "U$3") (pin "22/A8") (pinfunction "22/A8/CTX1_22/A8") (pintype "bidirectional"))
    )
    (net (code "77") (name "MSTEP_08") (class "Default")
      (node (ref "MOTOR_08") (pin "STEP") (pinfunction "STEP_STEP") (pintype "bidirectional"))
      (node (ref "U$3") (pin "26") (pinfunction "26/A12/MOSI1_26") (pintype "bidirectional"))
    )
    (net (code "78") (name "NEO_PIXEL") (class "Default")
      (node (ref "CONN01") (pin "5") (pinfunction "5_5") (pintype "bidirectional"))
      (node (ref "U$3") (pin "3") (pinfunction "3_3") (pintype "bidirectional"))
    )
    (net (code "79") (name "Net-(C5-Pad1)") (class "Default")
      (node (ref "C5") (pin "1") (pinfunction "1_1") (pintype "passive"))
      (node (ref "R7") (pin "1") (pinfunction "1_1") (pintype "passive"))
      (node (ref "R8") (pin "2") (pinfunction "2_2") (pintype "passive"))
    )
    (net (code "80") (name "Net-(C7-Pad2)") (class "Default")
      (node (ref "C7") (pin "2") (pinfunction "2_2") (pintype "passive"))
      (node (ref "C8") (pin "1") (pinfunction "1_1") (pintype "passive"))
    )
    (net (code "81") (name "Net-(C9-Pad1)") (class "Default")
      (node (ref "C9") (pin "1") (pinfunction "1_1") (pintype "passive"))
      (node (ref "U$2") (pin "VCAPH") (pinfunction "VCAPH_VCAPH") (pintype "bidirectional"))
    )
    (net (code "82") (name "Net-(C9-Pad2)") (class "Default")
      (node (ref "C9") (pin "2") (pinfunction "2_2") (pintype "passive"))
      (node (ref "U$2") (pin "VCAPL") (pinfunction "VCAPL_VCAPL") (pintype "bidirectional"))
    )
    (net (code "83") (name "Net-(CAN_INPUT-1)") (class "Default")
      (node (ref "CAN_INPUT") (pin "2") (pinfunction "1_2") (pintype "passive"))
      (node (ref "CAN_INPUT1") (pin "2") (pinfunction "1_2") (pintype "passive"))
      (node (ref "D3") (pin "2") (pinfunction "2_2") (pintype "passive"))
      (node (ref "J1") (pin "2") (pinfunction "2_2") (pintype "passive"))
      (node (ref "U$1") (pin "CANL") (pinfunction "CANL_CANL") (pintype "bidirectional"))
    )
    (net (code "84") (name "Net-(CAN_INPUT-2)") (class "Default")
      (node (ref "CAN_INPUT") (pin "1") (pinfunction "2_1") (pintype "passive"))
      (node (ref "CAN_INPUT1") (pin "1") (pinfunction "2_1") (pintype "passive"))
      (node (ref "D3") (pin "1") (pinfunction "1_1") (pintype "passive"))
      (node (ref "R7") (pin "2") (pinfunction "2_2") (pintype "passive"))
      (node (ref "U$1") (pin "CANH") (pinfunction "CANH_CANH") (pintype "bidirectional"))
    )
    (net (code "85") (name "Net-(D1-PadA)") (class "Default")
      (node (ref "D1") (pin "A") (pinfunction "A_A") (pintype "passive"))
      (node (ref "D2") (pin "A") (pinfunction "A_A") (pintype "passive"))
    )
    (net (code "86") (name "Net-(J1-Pad1)") (class "Default")
      (node (ref "J1") (pin "1") (pinfunction "1_1") (pintype "passive"))
      (node (ref "R8") (pin "1") (pinfunction "1_1") (pintype "passive"))
    )
    (net (code "87") (name "Net-(R2-Pad2)") (class "Default")
      (node (ref "R2") (pin "2") (pinfunction "2_2") (pintype "passive"))
      (node (ref "SJ1") (pin "3") (pinfunction "3_3") (pintype "passive"))
    )
    (net (code "88") (name "Net-(R4-Pad2)") (class "Default")
      (node (ref "R4") (pin "2") (pinfunction "2_2") (pintype "passive"))
      (node (ref "SJ1") (pin "1") (pinfunction "1_1") (pintype "passive"))
    )
    (net (code "89") (name "Net-(R5-Pad1)") (class "Default")
      (node (ref "R5") (pin "1") (pinfunction "1_1") (pintype "passive"))
      (node (ref "SJ4") (pin "1") (pinfunction "1_1") (pintype "passive"))
    )
    (net (code "90") (name "Net-(R6-Pad1)") (class "Default")
      (node (ref "R6") (pin "1") (pinfunction "1_1") (pintype "passive"))
      (node (ref "SJ5") (pin "1") (pinfunction "1_1") (pintype "passive"))
    )
    (net (code "91") (name "Net-(STATUS_LED-A)") (class "Default")
      (node (ref "R10") (pin "1") (pinfunction "1_1") (pintype "passive"))
      (node (ref "STATUS_LED") (pin "1") (pinfunction "A_1") (pintype "passive"))
    )
    (net (code "92") (name "Net-(U$1-STB)") (class "Default")
      (node (ref "R9") (pin "1") (pinfunction "1_1") (pintype "passive"))
      (node (ref "U$1") (pin "RS") (pinfunction "STB_RS") (pintype "input"))
    )
    (net (code "93") (name "Net-(U$4-IN)") (class "Default")
      (node (ref "U$2") (pin "GDRIVE") (pinfunction "GDRIVE_GDRIVE") (pintype "bidirectional"))
      (node (ref "U$2") (pin "GPD") (pinfunction "GPD_GPD") (pintype "bidirectional"))
      (node (ref "U$4") (pin "1") (pinfunction "IN_1") (pintype "input"))
    )
    (net (code "94") (name "OSCIO_SX0") (class "Default")
      (node (ref "U1") (pin "11") (pinfunction "OSCIO_11") (pintype "bidirectional"))
    )
    (net (code "95") (name "PIN_2") (class "Default")
      (node (ref "CONN01") (pin "6") (pinfunction "6_6") (pintype "bidirectional"))
      (node (ref "U$3") (pin "2") (pinfunction "2_2") (pintype "bidirectional"))
    )
    (net (code "96") (name "REG_5V") (class "Default")
      (node (ref "C15") (pin "+") (pinfunction "+_+") (pintype "passive"))
      (node (ref "S1") (pin "6") (pinfunction "6_6") (pintype "bidirectional"))
      (node (ref "U$2") (pin "CATHODE") (pinfunction "CATHODE_CATHODE") (pintype "bidirectional"))
      (node (ref "U$4") (pin "4") (pinfunction "GND_4") (pintype "input"))
    )
    (net (code "97") (name "SCL_00") (class "Default")
      (node (ref "R2") (pin "1") (pinfunction "1_1") (pintype "passive"))
      (node (ref "U$3") (pin "19/A5") (pinfunction "19/A5/SCL0_19/A5") (pintype "bidirectional"))
      (node (ref "U1") (pin "25") (pinfunction "SCL_25") (pintype "bidirectional"))
    )
    (net (code "98") (name "SCL_01") (class "Default")
      (node (ref "CONN01") (pin "1") (pinfunction "1_1") (pintype "bidirectional"))
      (node (ref "U$3") (pin "16/A2") (pinfunction "16/A2/SCL1_16/A2") (pintype "bidirectional"))
    )
    (net (code "99") (name "SCL_02") (class "Default")
      (node (ref "CONN01") (pin "3") (pinfunction "3_3") (pintype "bidirectional"))
      (node (ref "U$3") (pin "24") (pinfunction "24/A10/SCL2_24") (pintype "bidirectional"))
    )
    (net (code "100") (name "SDA_00") (class "Default")
      (node (ref "R4") (pin "1") (pinfunction "1_1") (pintype "passive"))
      (node (ref "U$3") (pin "18/A4") (pinfunction "18/A4/SDA0_18/A4") (pintype "bidirectional"))
      (node (ref "U1") (pin "24") (pinfunction "SDA_24") (pintype "bidirectional"))
    )
    (net (code "101") (name "SDA_01") (class "Default")
      (node (ref "CONN01") (pin "2") (pinfunction "2_2") (pintype "bidirectional"))
      (node (ref "U$3") (pin "17/A3") (pinfunction "17/A3/SDA1_17/A3") (pintype "bidirectional"))
    )
    (net (code "102") (name "SDA_02") (class "Default")
      (node (ref "CONN01") (pin "4") (pinfunction "4_4") (pintype "bidirectional"))
      (node (ref "U$3") (pin "25") (pinfunction "25/A11/SDA2_25") (pintype "bidirectional"))
    )
    (net (code "103") (name "STATUS_PIN") (class "Default")
      (node (ref "R10") (pin "2") (pinfunction "2_2") (pintype "passive"))
      (node (ref "U$3") (pin "4") (pinfunction "4_4") (pintype "bidirectional"))
    )
    (net (code "104") (name "TRQ1") (class "Default")
      (node (ref "MOTOR_01") (pin "1") (pinfunction "1_1") (pintype "bidirectional"))
      (node (ref "MOTOR_02") (pin "1") (pinfunction "1_1") (pintype "bidirectional"))
      (node (ref "MOTOR_03") (pin "1") (pinfunction "1_1") (pintype "bidirectional"))
      (node (ref "MOTOR_04") (pin "1") (pinfunction "1_1") (pintype "bidirectional"))
      (node (ref "MOTOR_05") (pin "1") (pinfunction "1_1") (pintype "bidirectional"))
      (node (ref "MOTOR_06") (pin "1") (pinfunction "1_1") (pintype "bidirectional"))
      (node (ref "MOTOR_07") (pin "1") (pinfunction "1_1") (pintype "bidirectional"))
      (node (ref "MOTOR_08") (pin "1") (pinfunction "1_1") (pintype "bidirectional"))
      (node (ref "U$3") (pin "32") (pinfunction "32_32") (pintype "bidirectional"))
    )
    (net (code "105") (name "TRQ2") (class "Default")
      (node (ref "MOTOR_01") (pin "2") (pinfunction "2_2") (pintype "bidirectional"))
      (node (ref "MOTOR_02") (pin "2") (pinfunction "2_2") (pintype "bidirectional"))
      (node (ref "MOTOR_03") (pin "2") (pinfunction "2_2") (pintype "bidirectional"))
      (node (ref "MOTOR_04") (pin "2") (pinfunction "2_2") (pintype "bidirectional"))
      (node (ref "MOTOR_05") (pin "2") (pinfunction "2_2") (pintype "bidirectional"))
      (node (ref "MOTOR_06") (pin "2") (pinfunction "2_2") (pintype "bidirectional"))
      (node (ref "MOTOR_07") (pin "2") (pinfunction "2_2") (pintype "bidirectional"))
      (node (ref "MOTOR_08") (pin "2") (pinfunction "2_2") (pintype "bidirectional"))
      (node (ref "U$3") (pin "33") (pinfunction "33_33") (pintype "bidirectional"))
    )
    (net (code "106") (name "VBAT") (class "Default")
      (node (ref "U$3") (pin "VBAT") (pinfunction "VBAT_VBAT") (pintype "power_in"))
    )
    (net (code "107") (name "VCC_5V") (class "Default")
      (node (ref "CONN01") (pin "11") (pinfunction "11_11") (pintype "bidirectional"))
      (node (ref "MOTOR_01") (pin "FAULT") (pinfunction "FAULT_FAULT") (pintype "bidirectional"))
      (node (ref "MOTOR_02") (pin "FAULT") (pinfunction "FAULT_FAULT") (pintype "bidirectional"))
      (node (ref "MOTOR_03") (pin "FAULT") (pinfunction "FAULT_FAULT") (pintype "bidirectional"))
      (node (ref "MOTOR_04") (pin "FAULT") (pinfunction "FAULT_FAULT") (pintype "bidirectional"))
      (node (ref "MOTOR_05") (pin "FAULT") (pinfunction "FAULT_FAULT") (pintype "bidirectional"))
      (node (ref "MOTOR_06") (pin "FAULT") (pinfunction "FAULT_FAULT") (pintype "bidirectional"))
      (node (ref "MOTOR_07") (pin "FAULT") (pinfunction "FAULT_FAULT") (pintype "bidirectional"))
      (node (ref "MOTOR_08") (pin "FAULT") (pinfunction "FAULT_FAULT") (pintype "bidirectional"))
      (node (ref "S1") (pin "2") (pinfunction "2_2") (pintype "bidirectional"))
      (node (ref "U$3") (pin "VIN") (pinfunction "VIN_VIN") (pintype "power_in"))
    )
    (net (code "108") (name "VCC_M") (class "Default")
      (node (ref "MC1") (pin "+") (pinfunction "+_+") (pintype "passive"))
      (node (ref "MC2") (pin "+") (pinfunction "+_+") (pintype "passive"))
      (node (ref "MC3") (pin "+") (pinfunction "+_+") (pintype "passive"))
      (node (ref "MC4") (pin "+") (pinfunction "+_+") (pintype "passive"))
      (node (ref "MC5") (pin "+") (pinfunction "+_+") (pintype "passive"))
      (node (ref "MC6") (pin "+") (pinfunction "+_+") (pintype "passive"))
      (node (ref "MC7") (pin "+") (pinfunction "+_+") (pintype "passive"))
      (node (ref "MC8") (pin "+") (pinfunction "+_+") (pintype "passive"))
      (node (ref "MOTOR_01") (pin "VM") (pinfunction "VM_VM") (pintype "bidirectional"))
      (node (ref "MOTOR_02") (pin "VM") (pinfunction "VM_VM") (pintype "bidirectional"))
      (node (ref "MOTOR_03") (pin "VM") (pinfunction "VM_VM") (pintype "bidirectional"))
      (node (ref "MOTOR_04") (pin "VM") (pinfunction "VM_VM") (pintype "bidirectional"))
      (node (ref "MOTOR_05") (pin "VM") (pinfunction "VM_VM") (pintype "bidirectional"))
      (node (ref "MOTOR_06") (pin "VM") (pinfunction "VM_VM") (pintype "bidirectional"))
      (node (ref "MOTOR_07") (pin "VM") (pinfunction "VM_VM") (pintype "bidirectional"))
      (node (ref "MOTOR_08") (pin "VM") (pinfunction "VM_VM") (pintype "bidirectional"))
      (node (ref "POWER_M") (pin "1") (pinfunction "1_1") (pintype "passive"))
    )
    (net (code "109") (name "VCC_MCU") (class "Default")
      (node (ref "C7") (pin "1") (pinfunction "1_1") (pintype "passive"))
      (node (ref "D1") (pin "C") (pinfunction "C_C") (pintype "passive"))
      (node (ref "POWER_MCU") (pin "1") (pinfunction "1_1") (pintype "passive"))
      (node (ref "U$2") (pin "ANODE") (pinfunction "ANODE_ANODE") (pintype "bidirectional"))
      (node (ref "U$4") (pin "3") (pinfunction "OUT_3") (pintype "passive"))
    )
    (net (code "110") (name "unconnected-(S1-Pad1)") (class "Default")
      (node (ref "S1") (pin "1") (pinfunction "1_1") (pintype "bidirectional"))
    )
    (net (code "111") (name "unconnected-(S1-Pad3)") (class "Default")
      (node (ref "S1") (pin "3") (pinfunction "3_3") (pintype "bidirectional"))
    )
    (net (code "112") (name "unconnected-(S1-Pad4)") (class "Default")
      (node (ref "S1") (pin "4") (pinfunction "4_4") (pintype "bidirectional"))
    )
    (net (code "113") (name "unconnected-(S1-Pad5)") (class "Default")
      (node (ref "S1") (pin "5") (pinfunction "5_5") (pintype "bidirectional"))
    )
    (net (code "114") (name "unconnected-(U$1-NC-PadVREF)") (class "Default")
      (node (ref "U$1") (pin "VREF") (pinfunction "NC_VREF") (pintype "passive"))
    )
    (net (code "115") (name "unconnected-(U$2-NC-PadNC@1)") (class "Default")
      (node (ref "U$2") (pin "NC@1") (pinfunction "NC_NC@1") (pintype "no_connect"))
    )
    (net (code "116") (name "unconnected-(U$2-NC-PadNC@2)") (class "Default")
      (node (ref "U$2") (pin "NC@2") (pinfunction "NC_NC@2") (pintype "no_connect"))
    )
    (net (code "117") (name "unconnected-(U$3-PadPGM)") (class "Default")
      (node (ref "U$3") (pin "PGM") (pinfunction "PGM_PGM") (pintype "bidirectional"))
    )
    (net (code "118") (name "unconnected-(U$3-PadRESET)") (class "Default")
      (node (ref "U$3") (pin "RESET") (pinfunction "RESET_RESET") (pintype "bidirectional"))
    )
    (net (code "119") (name "~{INT_SX0}") (class "Default")
      (node (ref "R1") (pin "1") (pinfunction "1_1") (pintype "passive"))
      (node (ref "U$3") (pin "13") (pinfunction "13/SCK/LED_13") (pintype "bidirectional"))
      (node (ref "U1") (pin "9") (pinfunction "~{INT}_9") (pintype "bidirectional"))
    )
    (net (code "120") (name "~{RESET_SX0}") (class "Default")
      (node (ref "R3") (pin "1") (pinfunction "1_1") (pintype "passive"))
      (node (ref "U1") (pin "23") (pinfunction "~{RESET}_23") (pintype "bidirectional"))
    )
  )
)
